# 02_PWR_IN.net
KiCad netlist of a schematic drawn in Altium Designer
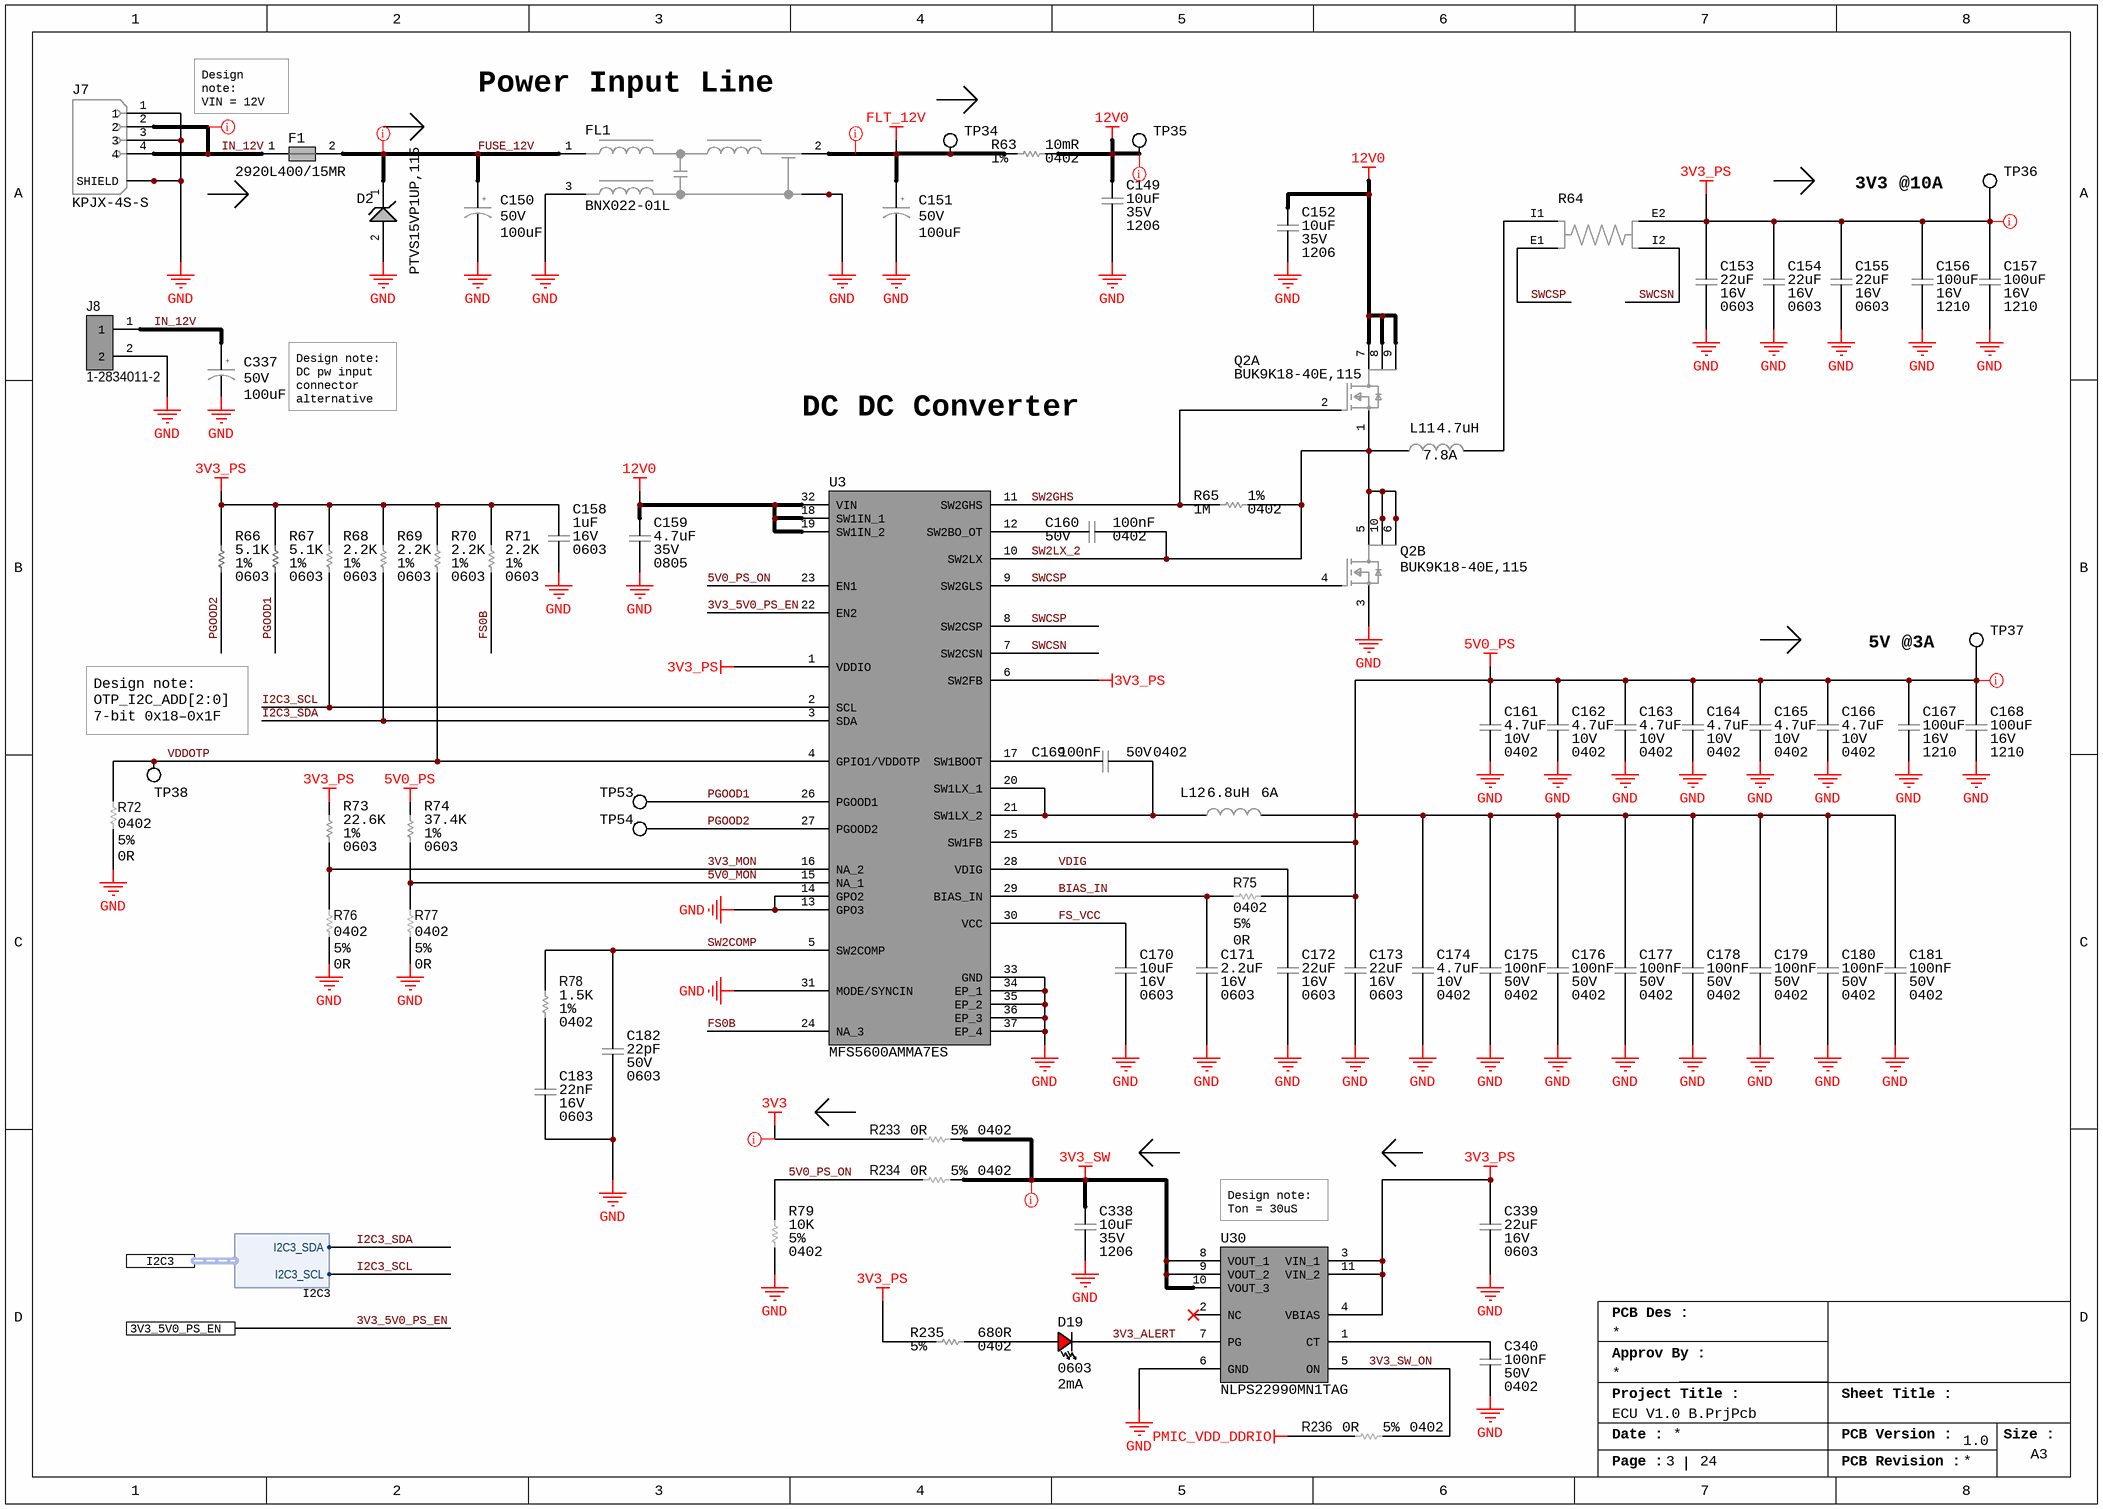
[diagram p0: 02_PWR IN.SchDoc]

(export (version "E")
  (design (tool "Eeschema 10.0.6"))
  (components
    (comp (ref "C149")
      (value "GRM319R6YA106KA12D")
      (footprint "CAP_1206_CAPC3216X16N")
      (description "1206 10 uF 35 V ±10 % Tolerance X5R SMT Multilayer Ceramic Capacitor")
      (fields
        (field (name "MANUFACTURER") "Murata")
        (field (name "TOLERANCE") "10%")
        (field (name "VOLTAGE RATING") "35V")
        (field (name "CAPACITANCE") "10uF")
        (field (name "CASE/PACKAGE") "1206")
      )
      (libsource (lib "Electronic Devices_LIB") (part "CAP_10uF_35V_X5R_1206"))
    )
    (comp (ref "C150")
      (value "UUD1H101MNL1GS")
      (footprint "CAP_POLA_UD(8X10)")
      (description "Radial Can - SMD ALUMINUM ELECTROLYTIC CAPACITOR UUD 50V 100muF ±20% 0.315Dia 8.00mm")
      (fields
        (field (name "MANUFACTURER") "Nichicon")
        (field (name "TOLERANCE") "20%")
        (field (name "VOLTAGE RATING (DC)") "50V")
        (field (name "CAPACITANCE") "100uF")
      )
      (libsource (lib "Electronic Devices_LIB") (part "CAP_100UF_50V_POL"))
    )
    (comp (ref "C151")
      (value "UUD1H101MNL1GS")
      (footprint "CAP_POLA_UD(8X10)")
      (description "Radial Can - SMD ALUMINUM ELECTROLYTIC CAPACITOR UUD 50V 100muF ±20% 0.315Dia 8.00mm")
      (fields
        (field (name "MANUFACTURER") "Nichicon")
        (field (name "TOLERANCE") "20%")
        (field (name "VOLTAGE RATING (DC)") "50V")
        (field (name "CAPACITANCE") "100uF")
      )
      (libsource (lib "Electronic Devices_LIB") (part "CAP_100UF_50V_POL"))
    )
    (comp (ref "C152")
      (value "GRM319R6YA106KA12D")
      (footprint "CAP_1206_CAPC3216X16N")
      (description "1206 10 uF 35 V ±10 % Tolerance X5R SMT Multilayer Ceramic Capacitor")
      (fields
        (field (name "MANUFACTURER") "Murata")
        (field (name "TOLERANCE") "10%")
        (field (name "VOLTAGE RATING") "35V")
        (field (name "CAPACITANCE") "10uF")
        (field (name "CASE/PACKAGE") "1206")
      )
      (libsource (lib "Electronic Devices_LIB") (part "CAP_10uF_35V_X5R_1206"))
    )
    (comp (ref "C153")
      (value "CL10A226MO7JZNC")
      (footprint "CAP_0603_CAPC1608X08N")
      (description "Cap Ceramic 22uF 16V X5R 20% Pad SMD 0603 85C T/R")
      (fields
        (field (name "MANUFACTURER") "Samsung")
        (field (name "TOLERANCE") "20%")
        (field (name "CAPACITANCE") "22uF")
        (field (name "VOLTAGE RATING") "16V")
        (field (name "CASE/PACKAGE") "0603")
      )
      (libsource (lib "Electronic Devices_LIB") (part "CAP_22UF_16V_X5R_0603"))
    )
    (comp (ref "C154")
      (value "CL10A226MO7JZNC")
      (footprint "CAP_0603_CAPC1608X08N")
      (description "Cap Ceramic 22uF 16V X5R 20% Pad SMD 0603 85C T/R")
      (fields
        (field (name "MANUFACTURER") "Samsung")
        (field (name "TOLERANCE") "20%")
        (field (name "CAPACITANCE") "22uF")
        (field (name "VOLTAGE RATING") "16V")
        (field (name "CASE/PACKAGE") "0603")
      )
      (libsource (lib "Electronic Devices_LIB") (part "CAP_22UF_16V_X5R_0603"))
    )
    (comp (ref "C155")
      (value "CL10A226MO7JZNC")
      (footprint "CAP_0603_CAPC1608X08N")
      (description "Cap Ceramic 22uF 16V X5R 20% Pad SMD 0603 85C T/R")
      (fields
        (field (name "MANUFACTURER") "Samsung")
        (field (name "TOLERANCE") "20%")
        (field (name "CAPACITANCE") "22uF")
        (field (name "VOLTAGE RATING") "16V")
        (field (name "CASE/PACKAGE") "0603")
      )
      (libsource (lib "Electronic Devices_LIB") (part "CAP_22UF_16V_X5R_0603"))
    )
    (comp (ref "C156")
      (value "EMK325ABJ107MM-T")
      (footprint "CAP_1210_CAPC3225X270N")
      (description "Multilayer Ceramic Capacitor, 100 uF, 16 V, ± 20%, X5R, 1210 [3225 Metric]")
      (fields
        (field (name "MANUFACTURER") "Taiyo Yuden")
        (field (name "TOLERANCE") "20%")
        (field (name "VOLTAGE RATING") "16V")
        (field (name "CAPACITANCE") "100uF")
        (field (name "CASE/PACKAGE") "1210")
      )
      (libsource (lib "Electronic Devices_LIB") (part "CAP_100UF_16V_X5R_1210"))
    )
    (comp (ref "C157")
      (value "EMK325ABJ107MM-T")
      (footprint "CAP_1210_CAPC3225X270N")
      (description "Multilayer Ceramic Capacitor, 100 uF, 16 V, ± 20%, X5R, 1210 [3225 Metric]")
      (fields
        (field (name "MANUFACTURER") "Taiyo Yuden")
        (field (name "TOLERANCE") "20%")
        (field (name "VOLTAGE RATING") "16V")
        (field (name "CAPACITANCE") "100uF")
        (field (name "CASE/PACKAGE") "1210")
      )
      (libsource (lib "Electronic Devices_LIB") (part "CAP_100UF_16V_X5R_1210"))
    )
    (comp (ref "C158")
      (value "CL10A105KO8NNNC")
      (footprint "CAP_0603_CAPC1608X08N")
      (description "CAP CER 1UF 16V X5R 0603")
      (fields
        (field (name "MANUFACTURER") "Samsung")
        (field (name "TOLERANCE") "10%")
        (field (name "VOLTAGE RATING") "16V")
        (field (name "CAPACITANCE") "1uF")
        (field (name "CASE/PACKAGE") "0603")
      )
      (libsource (lib "Electronic Devices_LIB") (part "CAP_1UF_16V_X5R_0603"))
    )
    (comp (ref "C159")
      (value "CL21A475KLCLQNC")
      (footprint "CAP_0805_CAPC2012X12N")
      (description "CL Series 0805 35 V 4.7 uF ±10% Tolerance X5R Multilayer Ceramic Chip Capacitor")
      (fields
        (field (name "MANUFACTURER") "Samsung")
        (field (name "TOLERANCE") "10%")
        (field (name "VOLTAGE RATING") "35V")
        (field (name "CAPACITANCE") "4.7uF")
        (field (name "CASE/PACKAGE") "0805")
      )
      (libsource (lib "Electronic Devices_LIB") (part "CAP_4.7uF_35V_X5R_0805"))
    )
    (comp (ref "C160")
      (value "GRM155R71H104KE14D")
      (footprint "CAP_0402_CAPC1005X05N")
      (description "Multilayer Ceramic Capacitor, 0.1 uF, 16 V, ± 10%, X7R, 0402 [1005 Metric]")
      (fields
        (field (name "MANUFACTURER") "Murata")
        (field (name "TOLERANCE") "10%")
        (field (name "VOLTAGE RATING") "50V")
        (field (name "CAPACITANCE") "100nF")
        (field (name "CASE/PACKAGE") "0402")
      )
      (libsource (lib "Electronic Devices_LIB") (part "CAP_100NF_50V_X7R_0402"))
    )
    (comp (ref "C161")
      (value "CL05A475KP5NRNC")
      (footprint "CAP_0402_CAPC1005X05N")
      (description "Multilayer Ceramic Capacitor, 4.7 uF, 10 V, ± 10%, X5R, 0402 [1005 Metric]")
      (fields
        (field (name "MANUFACTURER") "Samsung")
        (field (name "TOLERANCE") "10%")
        (field (name "CAPACITANCE") "4.7uF")
        (field (name "VOLTAGE RATING") "10V")
        (field (name "CASE/PACKAGE") "0402")
      )
      (libsource (lib "Electronic Devices_LIB") (part "CAP_4.7UF_10V_X5R_0402"))
    )
    (comp (ref "C162")
      (value "CL05A475KP5NRNC")
      (footprint "CAP_0402_CAPC1005X05N")
      (description "Multilayer Ceramic Capacitor, 4.7 uF, 10 V, ± 10%, X5R, 0402 [1005 Metric]")
      (fields
        (field (name "MANUFACTURER") "Samsung")
        (field (name "TOLERANCE") "10%")
        (field (name "CAPACITANCE") "4.7uF")
        (field (name "VOLTAGE RATING") "10V")
        (field (name "CASE/PACKAGE") "0402")
      )
      (libsource (lib "Electronic Devices_LIB") (part "CAP_4.7UF_10V_X5R_0402"))
    )
    (comp (ref "C163")
      (value "CL05A475KP5NRNC")
      (footprint "CAP_0402_CAPC1005X05N")
      (description "Multilayer Ceramic Capacitor, 4.7 uF, 10 V, ± 10%, X5R, 0402 [1005 Metric]")
      (fields
        (field (name "MANUFACTURER") "Samsung")
        (field (name "TOLERANCE") "10%")
        (field (name "CAPACITANCE") "4.7uF")
        (field (name "VOLTAGE RATING") "10V")
        (field (name "CASE/PACKAGE") "0402")
      )
      (libsource (lib "Electronic Devices_LIB") (part "CAP_4.7UF_10V_X5R_0402"))
    )
    (comp (ref "C164")
      (value "CL05A475KP5NRNC")
      (footprint "CAP_0402_CAPC1005X05N")
      (description "Multilayer Ceramic Capacitor, 4.7 uF, 10 V, ± 10%, X5R, 0402 [1005 Metric]")
      (fields
        (field (name "MANUFACTURER") "Samsung")
        (field (name "TOLERANCE") "10%")
        (field (name "CAPACITANCE") "4.7uF")
        (field (name "VOLTAGE RATING") "10V")
        (field (name "CASE/PACKAGE") "0402")
      )
      (libsource (lib "Electronic Devices_LIB") (part "CAP_4.7UF_10V_X5R_0402"))
    )
    (comp (ref "C165")
      (value "CL05A475KP5NRNC")
      (footprint "CAP_0402_CAPC1005X05N")
      (description "Multilayer Ceramic Capacitor, 4.7 uF, 10 V, ± 10%, X5R, 0402 [1005 Metric]")
      (fields
        (field (name "MANUFACTURER") "Samsung")
        (field (name "TOLERANCE") "10%")
        (field (name "CAPACITANCE") "4.7uF")
        (field (name "VOLTAGE RATING") "10V")
        (field (name "CASE/PACKAGE") "0402")
      )
      (libsource (lib "Electronic Devices_LIB") (part "CAP_4.7UF_10V_X5R_0402"))
    )
    (comp (ref "C166")
      (value "CL05A475KP5NRNC")
      (footprint "CAP_0402_CAPC1005X05N")
      (description "Multilayer Ceramic Capacitor, 4.7 uF, 10 V, ± 10%, X5R, 0402 [1005 Metric]")
      (fields
        (field (name "MANUFACTURER") "Samsung")
        (field (name "TOLERANCE") "10%")
        (field (name "CAPACITANCE") "4.7uF")
        (field (name "VOLTAGE RATING") "10V")
        (field (name "CASE/PACKAGE") "0402")
      )
      (libsource (lib "Electronic Devices_LIB") (part "CAP_4.7UF_10V_X5R_0402"))
    )
    (comp (ref "C167")
      (value "EMK325ABJ107MM-T")
      (footprint "CAP_1210_CAPC3225X270N")
      (description "Multilayer Ceramic Capacitor, 100 uF, 16 V, ± 20%, X5R, 1210 [3225 Metric]")
      (fields
        (field (name "MANUFACTURER") "Taiyo Yuden")
        (field (name "TOLERANCE") "20%")
        (field (name "VOLTAGE RATING") "16V")
        (field (name "CAPACITANCE") "100uF")
        (field (name "CASE/PACKAGE") "1210")
      )
      (libsource (lib "Electronic Devices_LIB") (part "CAP_100UF_16V_X5R_1210"))
    )
    (comp (ref "C168")
      (value "EMK325ABJ107MM-T")
      (footprint "CAP_1210_CAPC3225X270N")
      (description "Multilayer Ceramic Capacitor, 100 uF, 16 V, ± 20%, X5R, 1210 [3225 Metric]")
      (fields
        (field (name "MANUFACTURER") "Taiyo Yuden")
        (field (name "TOLERANCE") "20%")
        (field (name "VOLTAGE RATING") "16V")
        (field (name "CAPACITANCE") "100uF")
        (field (name "CASE/PACKAGE") "1210")
      )
      (libsource (lib "Electronic Devices_LIB") (part "CAP_100UF_16V_X5R_1210"))
    )
    (comp (ref "C169")
      (value "GRM155R71H104KE14D")
      (footprint "CAP_0402_CAPC1005X05N")
      (description "Multilayer Ceramic Capacitor, 0.1 uF, 16 V, ± 10%, X7R, 0402 [1005 Metric]")
      (fields
        (field (name "MANUFACTURER") "Murata")
        (field (name "TOLERANCE") "10%")
        (field (name "VOLTAGE RATING") "50V")
        (field (name "CAPACITANCE") "100nF")
        (field (name "CASE/PACKAGE") "0402")
      )
      (libsource (lib "Electronic Devices_LIB") (part "CAP_100NF_50V_X7R_0402"))
    )
    (comp (ref "C170")
      (value "GRM188R61C106MAALD")
      (footprint "CAP_0603_CAPC1608X08N")
      (description "0603 10 uF 16 V ±20% Tolerance X5R Multilayer Ceramic Chip Capacitor")
      (fields
        (field (name "MANUFACTURER") "Murata")
        (field (name "TOLERANCE") "20%")
        (field (name "VOLTAGE RATING") "16V")
        (field (name "CAPACITANCE") "10uF")
        (field (name "CASE/PACKAGE") "0603")
      )
      (libsource (lib "Electronic Devices_LIB") (part "CAP_10UF_16V_X5R_0603"))
    )
    (comp (ref "C171")
      (value "EMK107BB7225KA-T")
      (footprint "CAP_0603_CAPC1608X08N")
      (description "Multilayer Ceramic Capacitors (High dielectric type), 16V, 2.2 uF, ± 10 %, 0603, X7R, RoHS")
      (fields
        (field (name "MANUFACTURER") "Taiyo Yuden")
        (field (name "TOLERANCE") "10%")
        (field (name "CASE/PACKAGE") "0603")
        (field (name "CAPACITANCE") "2.2uF")
        (field (name "VOLTAGE RATING") "16V")
      )
      (libsource (lib "Electronic Devices_LIB") (part "CAP_2.2UF_16V_X7R_0603"))
    )
    (comp (ref "C172")
      (value "CL10A226MO7JZNC")
      (footprint "CAP_0603_CAPC1608X08N")
      (description "Cap Ceramic 22uF 16V X5R 20% Pad SMD 0603 85C T/R")
      (fields
        (field (name "MANUFACTURER") "Samsung")
        (field (name "TOLERANCE") "20%")
        (field (name "CAPACITANCE") "22uF")
        (field (name "VOLTAGE RATING") "16V")
        (field (name "CASE/PACKAGE") "0603")
      )
      (libsource (lib "Electronic Devices_LIB") (part "CAP_22UF_16V_X5R_0603"))
    )
    (comp (ref "C173")
      (value "CL10A226MO7JZNC")
      (footprint "CAP_0603_CAPC1608X08N")
      (description "Cap Ceramic 22uF 16V X5R 20% Pad SMD 0603 85C T/R")
      (fields
        (field (name "MANUFACTURER") "Samsung")
        (field (name "TOLERANCE") "20%")
        (field (name "CAPACITANCE") "22uF")
        (field (name "VOLTAGE RATING") "16V")
        (field (name "CASE/PACKAGE") "0603")
      )
      (libsource (lib "Electronic Devices_LIB") (part "CAP_22UF_16V_X5R_0603"))
    )
    (comp (ref "C174")
      (value "CL05A475KP5NRNC")
      (footprint "CAP_0402_CAPC1005X05N")
      (description "Multilayer Ceramic Capacitor, 4.7 uF, 10 V, ± 10%, X5R, 0402 [1005 Metric]")
      (fields
        (field (name "MANUFACTURER") "Samsung")
        (field (name "TOLERANCE") "10%")
        (field (name "CAPACITANCE") "4.7uF")
        (field (name "VOLTAGE RATING") "10V")
        (field (name "CASE/PACKAGE") "0402")
      )
      (libsource (lib "Electronic Devices_LIB") (part "CAP_4.7UF_10V_X5R_0402"))
    )
    (comp (ref "C175")
      (value "GRM155R71H104KE14D")
      (footprint "CAP_0402_CAPC1005X05N")
      (description "Multilayer Ceramic Capacitor, 0.1 uF, 16 V, ± 10%, X7R, 0402 [1005 Metric]")
      (fields
        (field (name "MANUFACTURER") "Murata")
        (field (name "TOLERANCE") "10%")
        (field (name "VOLTAGE RATING") "50V")
        (field (name "CAPACITANCE") "100nF")
        (field (name "CASE/PACKAGE") "0402")
      )
      (libsource (lib "Electronic Devices_LIB") (part "CAP_100NF_50V_X7R_0402"))
    )
    (comp (ref "C176")
      (value "GRM155R71H104KE14D")
      (footprint "CAP_0402_CAPC1005X05N")
      (description "Multilayer Ceramic Capacitor, 0.1 uF, 16 V, ± 10%, X7R, 0402 [1005 Metric]")
      (fields
        (field (name "MANUFACTURER") "Murata")
        (field (name "TOLERANCE") "10%")
        (field (name "VOLTAGE RATING") "50V")
        (field (name "CAPACITANCE") "100nF")
        (field (name "CASE/PACKAGE") "0402")
      )
      (libsource (lib "Electronic Devices_LIB") (part "CAP_100NF_50V_X7R_0402"))
    )
    (comp (ref "C177")
      (value "GRM155R71H104KE14D")
      (footprint "CAP_0402_CAPC1005X05N")
      (description "Multilayer Ceramic Capacitor, 0.1 uF, 16 V, ± 10%, X7R, 0402 [1005 Metric]")
      (fields
        (field (name "MANUFACTURER") "Murata")
        (field (name "TOLERANCE") "10%")
        (field (name "VOLTAGE RATING") "50V")
        (field (name "CAPACITANCE") "100nF")
        (field (name "CASE/PACKAGE") "0402")
      )
      (libsource (lib "Electronic Devices_LIB") (part "CAP_100NF_50V_X7R_0402"))
    )
    (comp (ref "C178")
      (value "GRM155R71H104KE14D")
      (footprint "CAP_0402_CAPC1005X05N")
      (description "Multilayer Ceramic Capacitor, 0.1 uF, 16 V, ± 10%, X7R, 0402 [1005 Metric]")
      (fields
        (field (name "MANUFACTURER") "Murata")
        (field (name "TOLERANCE") "10%")
        (field (name "VOLTAGE RATING") "50V")
        (field (name "CAPACITANCE") "100nF")
        (field (name "CASE/PACKAGE") "0402")
      )
      (libsource (lib "Electronic Devices_LIB") (part "CAP_100NF_50V_X7R_0402"))
    )
    (comp (ref "C179")
      (value "GRM155R71H104KE14D")
      (footprint "CAP_0402_CAPC1005X05N")
      (description "Multilayer Ceramic Capacitor, 0.1 uF, 16 V, ± 10%, X7R, 0402 [1005 Metric]")
      (fields
        (field (name "MANUFACTURER") "Murata")
        (field (name "TOLERANCE") "10%")
        (field (name "VOLTAGE RATING") "50V")
        (field (name "CAPACITANCE") "100nF")
        (field (name "CASE/PACKAGE") "0402")
      )
      (libsource (lib "Electronic Devices_LIB") (part "CAP_100NF_50V_X7R_0402"))
    )
    (comp (ref "C180")
      (value "GRM155R71H104KE14D")
      (footprint "CAP_0402_CAPC1005X05N")
      (description "Multilayer Ceramic Capacitor, 0.1 uF, 16 V, ± 10%, X7R, 0402 [1005 Metric]")
      (fields
        (field (name "MANUFACTURER") "Murata")
        (field (name "TOLERANCE") "10%")
        (field (name "VOLTAGE RATING") "50V")
        (field (name "CAPACITANCE") "100nF")
        (field (name "CASE/PACKAGE") "0402")
      )
      (libsource (lib "Electronic Devices_LIB") (part "CAP_100NF_50V_X7R_0402"))
    )
    (comp (ref "C181")
      (value "GRM155R71H104KE14D")
      (footprint "CAP_0402_CAPC1005X05N")
      (description "Multilayer Ceramic Capacitor, 0.1 uF, 16 V, ± 10%, X7R, 0402 [1005 Metric]")
      (fields
        (field (name "MANUFACTURER") "Murata")
        (field (name "TOLERANCE") "10%")
        (field (name "VOLTAGE RATING") "50V")
        (field (name "CAPACITANCE") "100nF")
        (field (name "CASE/PACKAGE") "0402")
      )
      (libsource (lib "Electronic Devices_LIB") (part "CAP_100NF_50V_X7R_0402"))
    )
    (comp (ref "C182")
      (value "C0603C220J5GACTU")
      (footprint "CAP_0603_CAPC1608X08N")
      (description "Multilayer Ceramic Capacitor, 22 pF, 50 V, ï¿½ 5%, C0G (NP0), 0603 [1608 Metric]")
      (fields
        (field (name "MANUFACTURER") "KEMET")
        (field (name "TOLERANCE") "5%")
        (field (name "VOLTAGE RATING (DC)") "50V")
        (field (name "CAPACITANCE") "22pF")
        (field (name "CASE/PACKAGE") "0603")
      )
      (libsource (lib "Electronic Devices_LIB") (part "CAP_22pF_50V_NP0_0603"))
    )
    (comp (ref "C183")
      (value "C0603C223K4RACTU")
      (footprint "CAP_0603_CAPC1608X08N")
      (description "Multilayer Ceramic Capacitor, 0.022 uF, 16 V, ± 10%, X7R, 0603 [1608 Metric]")
      (fields
        (field (name "MANUFACTURER") "KEMET")
        (field (name "TOLERANCE") "10%")
        (field (name "VOLTAGE RATING (DC)") "16V")
        (field (name "CAPACITANCE") "22nF")
        (field (name "CASE/PACKAGE") "0603")
      )
      (libsource (lib "Electronic Devices_LIB") (part "CAP_22nF_16V_X7R_0603"))
    )
    (comp (ref "C337")
      (value "UUD1H101MNL1GS")
      (footprint "CAP_POLA_UD(8X10)")
      (description "Radial Can - SMD ALUMINUM ELECTROLYTIC CAPACITOR UUD 50V 100muF ±20% 0.315Dia 8.00mm")
      (fields
        (field (name "MANUFACTURER") "Nichicon")
        (field (name "TOLERANCE") "20%")
        (field (name "VOLTAGE RATING (DC)") "50V")
        (field (name "CAPACITANCE") "100uF")
      )
      (libsource (lib "Electronic Devices_LIB") (part "CAP_100UF_50V_POL"))
    )
    (comp (ref "C338")
      (value "GRM319R6YA106KA12D")
      (footprint "CAP_1206_CAPC3216X16N")
      (description "1206 10 uF 35 V ±10 % Tolerance X5R SMT Multilayer Ceramic Capacitor")
      (fields
        (field (name "MANUFACTURER") "Murata")
        (field (name "TOLERANCE") "10%")
        (field (name "VOLTAGE RATING") "35V")
        (field (name "CAPACITANCE") "10uF")
        (field (name "CASE/PACKAGE") "1206")
      )
      (libsource (lib "Electronic Devices_LIB") (part "CAP_10uF_35V_X5R_1206"))
    )
    (comp (ref "C339")
      (value "CL10A226MO7JZNC")
      (footprint "CAP_0603_CAPC1608X08N")
      (description "Cap Ceramic 22uF 16V X5R 20% Pad SMD 0603 85C T/R")
      (fields
        (field (name "MANUFACTURER") "Samsung")
        (field (name "TOLERANCE") "20%")
        (field (name "CAPACITANCE") "22uF")
        (field (name "VOLTAGE RATING") "16V")
        (field (name "CASE/PACKAGE") "0603")
      )
      (libsource (lib "Electronic Devices_LIB") (part "CAP_22UF_16V_X5R_0603"))
    )
    (comp (ref "C340")
      (value "GRM155R71H104KE14D")
      (footprint "CAP_0402_CAPC1005X05N")
      (description "Multilayer Ceramic Capacitor, 0.1 uF, 16 V, ± 10%, X7R, 0402 [1005 Metric]")
      (fields
        (field (name "MANUFACTURER") "Murata")
        (field (name "TOLERANCE") "10%")
        (field (name "VOLTAGE RATING") "50V")
        (field (name "CAPACITANCE") "100nF")
        (field (name "CASE/PACKAGE") "0402")
      )
      (libsource (lib "Electronic Devices_LIB") (part "CAP_100NF_50V_X7R_0402"))
    )
    (comp (ref "D2")
      (value "PTVS15VP1UP,115")
      (footprint "PMEG3050EP115")
      (description "TVS DIODE 15VWM 24.4VC SOD128")
      (fields (field (name "MANUFACTURER") "Nexperia"))
      (libsource (lib "Electronic Devices_LIB") (part "DIO_TVS_24.4V_PTVS15VP1UP,115"))
    )
    (comp (ref "D19")
      (value "LTST-C193KRKT-2A")
      (footprint "LED_0603-RED-0.75mm")
      (description "Led Red Clear 0603 Smd")
      (fields
        (field (name "MANUFACTURER") "Vishay Lite-On")
        (field (name "CASE/PACKAGE") "0603")
        (field (name "TEST CURRENT") "2mA")
      )
      (libsource (lib "Electronic Devices_LIB") (part "LED_DIO_RED_2mA_0603_LTST-C193KRKT-2A"))
    )
    (comp (ref "F1")
      (value "2920L400/15MR")
      (footprint "2920L07560MR")
      (description "PTC Resettable Fuse 4A(hold) 8A(trip) 15VDC 40A 1.5W 4s 0.01Ohm SMD Solder Pad 2920 T/R")
      (fields (field (name "MANUFACTURER") "Littelfuse"))
      (libsource (lib "Electronic Devices_LIB") (part "FUSE_PTC_8A_2920L400/15MR"))
    )
    (comp (ref "FL1")
      (value "BNX022-01L")
      (footprint "FILTER_BNX022-01L")
      (description "EMI Filter 1MHz to 1000MHz 35dB 10A 50VDC Flat Style SMD Embossed T/R")
      (fields (field (name "MANUFACTURER") "Murata"))
      (libsource (lib "Electronic Devices_LIB") (part "FILTER_EMI_50VDC_10A_BNX022-01L"))
    )
    (comp (ref "J7")
      (value "KPJX-4S-S")
      (footprint "CONN_DC_KYCON_KPJX-4S-S")
      (description "Conn Power SKT 4 POS Solder ST Thru-Hole 4 Terminal 1 Port")
      (fields (field (name "MANUFACTURER") "Kycon"))
      (libsource (lib "Electronic Devices_LIB") (part "CONN_DC_JACK_PWR_KPJX-4S-S"))
    )
    (comp (ref "J8")
      (value "1-2834011-2")
      (footprint "CONN_TBLOCK_128340112")
      (description "2POS3.5MMTOPENTRYSCREWLESSC")
      (fields (field (name "MANUFACTURER") "TE Connectivity") (field (name "VOLTAGE") "300V"))
      (libsource (lib "Electronic Devices_LIB") (part "CONN_TBLOCK_2P_3.5mm_1-2834011-2"))
    )
    (comp (ref "L11")
      (value "SPM7054VT-4R7M-D")
      (footprint "SPM7054VT")
      (description "Inductor Power Shielded Wirewound 4.7uH 20% 100KHz Metal 7.8A 0.01826Ohm DCR Automotive T/R")
      (fields
        (field (name "MANUFACTURER") "TDK")
        (field (name "CURRENT RATING") "7.8A")
        (field (name "INDUCTANCE") "4.7uH")
      )
      (libsource (lib "Electronic Devices_LIB") (part "IND_4.7uH_7.8A_SPM7054VT-4R7M-D"))
    )
    (comp (ref "L12")
      (value "74437368068")
      (footprint "WE-LHMI_104048")
      (description "WE-LHMI; 6800 nH; Composite Iron Multilayer SMD Inductor; 1040 Case; .013GHz 6A")
      (fields
        (field (name "MANUFACTURER") "Wurth Electronics")
        (field (name "TOLERANCE") "20%")
        (field (name "MAX DC CURRENT") "6A")
        (field (name "INDUCTANCE") "6.8uH")
      )
      (libsource (lib "Electronic Devices_LIB") (part "IND_6.8uH_6A_74437368068"))
    )
    (comp (ref "Q2")
      (value "BUK9K18-40E,115")
      (footprint "BUK9K1840E115")
      (description "Transistor MOSFET Array Dual N -CH 40V 30A 8-Pin LFPAK-56D T/R")
      (fields (field (name "MANUFACTURER") "Nexperia"))
      (libsource (lib "Electronic Devices_LIB") (part "TRANS_FET_CH__N_40V_30A_BUK9K18-40E,115"))
    )
    (comp (ref "R63")
      (value "ERJ-2LWFR010X")
      (footprint "RES_0603_RESC1608X04N")
      (description "Res Current Sense Thick Film 0402 0.01 Ohm 1% 1/5W 0ppm/°C to 500ppm/°C Molded T/R")
      (fields
        (field (name "MANUFACTURER") "Panasonic")
        (field (name "TOLERANCE") "1%")
        (field (name "RESISTANCE") "10mR")
        (field (name "CASE/PACKAGE") "0402")
      )
      (libsource (lib "Electronic Devices_LIB") (part "RES_10mR_1%_0.05W_0402"))
    )
    (comp (ref "R64")
      (value "WSK2512R0100FEA")
      (footprint "RES_WSK2512R0100FEA")
      (description "Fixed Resistor, Metal Strip, 1W, 0.01ohm, 0.1V, 1% +/-Tol, 35ppm/Cel, Surface Mount, 2512")
      (fields (field (name "MANUFACTURER") "Vishay") (field (name "TOLERANCE") "1%"))
      (libsource (lib "Electronic Devices_LIB") (part "RES_10mR_1%_1W_2512"))
    )
    (comp (ref "R65")
      (value "CR0402-FX-1004GLF")
      (footprint "RES_0402_RESC1005X04N")
      (description "Res Thick Film 0402 1M Ohm 1% 1/16W ±100ppm/°C Molded SMD SMD Paper Tape on Plastic Reel")
      (fields
        (field (name "MANUFACTURER") "Bourns")
        (field (name "RESISTANCE") "1M")
        (field (name "TOLERANCE") "1%")
        (field (name "CASE/PACKAGE") "0402")
      )
      (libsource (lib "Electronic Devices_LIB") (part "RES_1M_1%_63mW_0402"))
    )
    (comp (ref "R66")
      (value "RC0603FR-075K1L")
      (footprint "RES_0603_RESC1608X04N")
      (description "SMD Chip Resistor, 5.1 kOhm, ± 1%, 100 mW, 0603 [1608 Metric], Thick Film, General Purpose")
      (fields
        (field (name "MANUFACTURER") "Yageo")
        (field (name "TOLERANCE") "1%")
        (field (name "RESISTANCE") "5.1K")
        (field (name "CASE/PACKAGE") "0603")
      )
      (libsource (lib "Electronic Devices_LIB") (part "RES_5.1K_1%_100mW_0603"))
    )
    (comp (ref "R67")
      (value "RC0603FR-075K1L")
      (footprint "RES_0603_RESC1608X04N")
      (description "SMD Chip Resistor, 5.1 kOhm, ± 1%, 100 mW, 0603 [1608 Metric], Thick Film, General Purpose")
      (fields
        (field (name "MANUFACTURER") "Yageo")
        (field (name "TOLERANCE") "1%")
        (field (name "RESISTANCE") "5.1K")
        (field (name "CASE/PACKAGE") "0603")
      )
      (libsource (lib "Electronic Devices_LIB") (part "RES_5.1K_1%_100mW_0603"))
    )
    (comp (ref "R68")
      (value "RC0603FR-072K2L")
      (footprint "RES_0603_RESC1608X04N")
      (description "SMD Chip Resistor, 2.2 Kohm, ½ 1%, 100 Mw, 0603 [1608 Metric], Thick Film, General Purpose")
      (fields
        (field (name "MANUFACTURER") "Yageo")
        (field (name "TOLERANCE") "1%")
        (field (name "RESISTANCE") "2.2K")
        (field (name "CASE/PACKAGE") "0603")
      )
      (libsource (lib "Electronic Devices_LIB") (part "RES_2.2K_1%_100mW_0603"))
    )
    (comp (ref "R69")
      (value "RC0603FR-072K2L")
      (footprint "RES_0603_RESC1608X04N")
      (description "SMD Chip Resistor, 2.2 Kohm, ½ 1%, 100 Mw, 0603 [1608 Metric], Thick Film, General Purpose")
      (fields
        (field (name "MANUFACTURER") "Yageo")
        (field (name "TOLERANCE") "1%")
        (field (name "RESISTANCE") "2.2K")
        (field (name "CASE/PACKAGE") "0603")
      )
      (libsource (lib "Electronic Devices_LIB") (part "RES_2.2K_1%_100mW_0603"))
    )
    (comp (ref "R70")
      (value "RC0603FR-072K2L")
      (footprint "RES_0603_RESC1608X04N")
      (description "SMD Chip Resistor, 2.2 Kohm, ½ 1%, 100 Mw, 0603 [1608 Metric], Thick Film, General Purpose")
      (fields
        (field (name "MANUFACTURER") "Yageo")
        (field (name "TOLERANCE") "1%")
        (field (name "RESISTANCE") "2.2K")
        (field (name "CASE/PACKAGE") "0603")
      )
      (libsource (lib "Electronic Devices_LIB") (part "RES_2.2K_1%_100mW_0603"))
    )
    (comp (ref "R71")
      (value "RC0603FR-072K2L")
      (footprint "RES_0603_RESC1608X04N")
      (description "SMD Chip Resistor, 2.2 Kohm, ½ 1%, 100 Mw, 0603 [1608 Metric], Thick Film, General Purpose")
      (fields
        (field (name "MANUFACTURER") "Yageo")
        (field (name "TOLERANCE") "1%")
        (field (name "RESISTANCE") "2.2K")
        (field (name "CASE/PACKAGE") "0603")
      )
      (libsource (lib "Electronic Devices_LIB") (part "RES_2.2K_1%_100mW_0603"))
    )
    (comp (ref "R72")
      (value "ERJ-2GE0R00X")
      (footprint "RES_0402_RESC1005X04N")
      (description "SMD Chip Resistor, Jumper, 0 ohm, 100 mW, 0402 [1005 Metric], Thick Film, General Purpose")
      (fields
        (field (name "MANUFACTURER") "Panasonic")
        (field (name "CASE CODE (IMPERIAL)") "0402")
        (field (name "TOLERANCE") "5%")
        (field (name "RESISTANCE") "0R")
      )
      (libsource (lib "Electronic Devices_LIB") (part "RES_0R_5%_100mW_0402"))
    )
    (comp (ref "R73")
      (value "AC0603FR-0722K6L")
      (footprint "RES_0603_RESC1608X04N")
      (description "Res Thick Film 0603 22.6K Ohm 1% 0.1W(1/10W) ±100ppm/C Pad SMD Automotive T/R")
      (fields
        (field (name "MANUFACTURER") "Yageo")
        (field (name "TOLERANCE") "1%")
        (field (name "RESISTANCE") "22.6K")
        (field (name "CASE/PACKAGE") "0603")
      )
      (libsource (lib "Electronic Devices_LIB") (part "RES_22.6K_1%_100mW_0603"))
    )
    (comp (ref "R74")
      (value "RC0603FR-0737K4L")
      (footprint "RES_0603_RESC1608X04N")
      (description "SMD Chip Resistor, 37.4 kOhm, ± 1%, 100 mW, 0603 [1608 Metric], Thick Film, General Purpose")
      (fields
        (field (name "MANUFACTURER") "Yageo")
        (field (name "TOLERANCE") "1%")
        (field (name "RESISTANCE") "37.4K")
        (field (name "CASE/PACKAGE") "0603")
      )
      (libsource (lib "Electronic Devices_LIB") (part "RES_37.4K_1%_100mW_0603"))
    )
    (comp (ref "R75")
      (value "ERJ-2GE0R00X")
      (footprint "RES_0402_RESC1005X04N")
      (description "SMD Chip Resistor, Jumper, 0 ohm, 100 mW, 0402 [1005 Metric], Thick Film, General Purpose")
      (fields
        (field (name "MANUFACTURER") "Panasonic")
        (field (name "CASE CODE (IMPERIAL)") "0402")
        (field (name "TOLERANCE") "5%")
        (field (name "RESISTANCE") "0R")
      )
      (libsource (lib "Electronic Devices_LIB") (part "RES_0R_5%_100mW_0402"))
    )
    (comp (ref "R76")
      (value "ERJ-2GE0R00X")
      (footprint "RES_0402_RESC1005X04N")
      (description "SMD Chip Resistor, Jumper, 0 ohm, 100 mW, 0402 [1005 Metric], Thick Film, General Purpose")
      (fields
        (field (name "MANUFACTURER") "Panasonic")
        (field (name "CASE CODE (IMPERIAL)") "0402")
        (field (name "TOLERANCE") "5%")
        (field (name "RESISTANCE") "0R")
      )
      (libsource (lib "Electronic Devices_LIB") (part "RES_0R_5%_100mW_0402"))
    )
    (comp (ref "R77")
      (value "ERJ-2GE0R00X")
      (footprint "RES_0402_RESC1005X04N")
      (description "SMD Chip Resistor, Jumper, 0 ohm, 100 mW, 0402 [1005 Metric], Thick Film, General Purpose")
      (fields
        (field (name "MANUFACTURER") "Panasonic")
        (field (name "CASE CODE (IMPERIAL)") "0402")
        (field (name "TOLERANCE") "5%")
        (field (name "RESISTANCE") "0R")
      )
      (libsource (lib "Electronic Devices_LIB") (part "RES_0R_5%_100mW_0402"))
    )
    (comp (ref "R78")
      (value "CR0402-FX-1501GLF")
      (footprint "RES_0402_RESC1005X04N")
      (description "Res Thick Film 0402 1.5K Ohm 1% 1/16W ±100ppm/°C Molded SMD SMD Paper Tape on Plastic Reel")
      (fields
        (field (name "MANUFACTURER") "Bourns")
        (field (name "RESISTANCE") "1.5K")
        (field (name "TOLERANCE") "1%")
        (field (name "CASE/PACKAGE") "0402")
      )
      (libsource (lib "Electronic Devices_LIB") (part "RES_1.5K_1%_63mW_0402"))
    )
    (comp (ref "R79")
      (value "ERJ-2GEJ103X")
      (footprint "RES_0402_RESC1005X04N")
      (description "Res Thick Film 0402 10K Ohm 5% 1/10W ±200ppm/°C Molded SMD Punched Carrier T/R")
      (fields
        (field (name "MANUFACTURER") "Panasonic")
        (field (name "TOLERANCE") "5%")
        (field (name "RESISTANCE") "10K")
        (field (name "CASE/PACKAGE") "0402")
      )
      (libsource (lib "Electronic Devices_LIB") (part "RES_10K_5%_100mW_0402"))
    )
    (comp (ref "R233")
      (value "ERJ-2GE0R00X")
      (footprint "RES_0402_RESC1005X04N")
      (description "SMD Chip Resistor, Jumper, 0 ohm, 100 mW, 0402 [1005 Metric], Thick Film, General Purpose")
      (fields
        (field (name "MANUFACTURER") "Panasonic")
        (field (name "CASE CODE (IMPERIAL)") "0402")
        (field (name "TOLERANCE") "5%")
        (field (name "RESISTANCE") "0R")
      )
      (libsource (lib "Electronic Devices_LIB") (part "RES_0R_5%_100mW_0402"))
    )
    (comp (ref "R234")
      (value "ERJ-2GE0R00X")
      (footprint "RES_0402_RESC1005X04N")
      (description "SMD Chip Resistor, Jumper, 0 ohm, 100 mW, 0402 [1005 Metric], Thick Film, General Purpose")
      (fields
        (field (name "MANUFACTURER") "Panasonic")
        (field (name "CASE CODE (IMPERIAL)") "0402")
        (field (name "TOLERANCE") "5%")
        (field (name "RESISTANCE") "0R")
      )
      (libsource (lib "Electronic Devices_LIB") (part "RES_0R_5%_100mW_0402"))
    )
    (comp (ref "R235")
      (value "ERJ-2GEJ681X")
      (footprint "RES_0402_RESC1005X04N")
      (description "SMD Chip Resistor, 680 Ohm, ± 5%, 100 mW, 0402 [1005 Metric], Thick Film, General Purpose")
      (fields
        (field (name "MANUFACTURER") "Panasonic")
        (field (name "TOLERANCE") "5%")
        (field (name "RESISTANCE") "680R")
        (field (name "CASE/PACKAGE") "0402")
      )
      (libsource (lib "Electronic Devices_LIB") (part "RES_680R_5%_100mW_0402"))
    )
    (comp (ref "R236")
      (value "ERJ-2GE0R00X")
      (footprint "RES_0402_RESC1005X04N")
      (description "SMD Chip Resistor, Jumper, 0 ohm, 100 mW, 0402 [1005 Metric], Thick Film, General Purpose")
      (fields
        (field (name "MANUFACTURER") "Panasonic")
        (field (name "CASE CODE (IMPERIAL)") "0402")
        (field (name "TOLERANCE") "5%")
        (field (name "RESISTANCE") "0R")
      )
      (libsource (lib "Electronic Devices_LIB") (part "RES_0R_5%_100mW_0402"))
    )
    (comp (ref "TP34")
      (value "NO COMPONENT")
      (footprint "TP_PAD_0.5MM_SMD_ROUND")
      (description "Test Point, SMD pad, round, 1.5mm, 1.6mm, 3mm diameter")
      (libsource (lib "Electronic Devices_LIB") (part "TP_PAD_SMD_SMALL"))
    )
    (comp (ref "TP35")
      (value "NO COMPONENT")
      (footprint "TP_PAD_0.5MM_SMD_ROUND")
      (description "Test Point, SMD pad, round, 1.5mm, 1.6mm, 3mm diameter")
      (libsource (lib "Electronic Devices_LIB") (part "TP_PAD_SMD_SMALL"))
    )
    (comp (ref "TP36")
      (value "NO COMPONENT")
      (footprint "TP_PAD_0.5MM_SMD_ROUND")
      (description "Test Point, SMD pad, round, 1.5mm, 1.6mm, 3mm diameter")
      (libsource (lib "Electronic Devices_LIB") (part "TP_PAD_SMD_SMALL"))
    )
    (comp (ref "TP37")
      (value "NO COMPONENT")
      (footprint "TP_PAD_0.5MM_SMD_ROUND")
      (description "Test Point, SMD pad, round, 1.5mm, 1.6mm, 3mm diameter")
      (libsource (lib "Electronic Devices_LIB") (part "TP_PAD_SMD_SMALL"))
    )
    (comp (ref "TP38")
      (value "NO COMPONENT")
      (footprint "TP_PAD_0.5MM_SMD_ROUND")
      (description "Test Point, SMD pad, round, 1.5mm, 1.6mm, 3mm diameter")
      (libsource (lib "Electronic Devices_LIB") (part "TP_PAD_SMD_SMALL"))
    )
    (comp (ref "TP53")
      (value "NO COMPONENT")
      (footprint "TP_PAD_0.5MM_SMD_ROUND")
      (description "Test Point, SMD pad, round, 1.5mm, 1.6mm, 3mm diameter")
      (libsource (lib "Electronic Devices_LIB") (part "TP_PAD_SMD_SMALL"))
    )
    (comp (ref "TP54")
      (value "NO COMPONENT")
      (footprint "TP_PAD_0.5MM_SMD_ROUND")
      (description "Test Point, SMD pad, round, 1.5mm, 1.6mm, 3mm diameter")
      (libsource (lib "Electronic Devices_LIB") (part "TP_PAD_SMD_SMALL"))
    )
    (comp (ref "U3")
      (value "MFS5600AMMA7ES")
      (footprint "MFS5600AMMA7ES")
      (description "Power Management, 36 V, 2 Step-Down DC-DC Converters, 2 Regulated Outputs, 32 Pins, HVQFN-EP")
      (fields (field (name "MANUFACTURER") "NXP Semiconductors"))
      (libsource (lib "Electronic Devices_LIB") (part "IC_REG_BUCK_MFS5600AMMA7ES"))
    )
    (comp (ref "U30")
      (value "NLPS22990MN1TAG")
      (footprint "SON50P200X300X80-11N")
      (description "5.5 V, 10 A, 3.9 mΩ On-Resistance Load Switch 5.5 V, 10 A, 3.9 mOhm On-Resistance")
      (fields (field (name "MANUFACTURER") "onsemi"))
      (libsource (lib "Electronic Devices_LIB") (part "IC_LOAD_SW_NLPS22990MN1TAG"))
    )
  )
  (nets
    (net (code "2") (name "/3V3_5V0_PS_EN") (class "Default")
      (node (ref "U3") (pin "22") (pinfunction "EN2_22") (pintype "passive"))
    )
    (net (code "3") (name "/3V3_ALERT") (class "Default")
      (node (ref "D19") (pin "1") (pinfunction "C_1") (pintype "passive"))
      (node (ref "U30") (pin "7") (pinfunction "PG_7") (pintype "passive"))
    )
    (net (code "4") (name "/3V3_MON") (class "Default")
      (node (ref "R73") (pin "1") (pinfunction "1_1") (pintype "passive"))
      (node (ref "R76") (pin "2") (pinfunction "2_2") (pintype "passive"))
      (node (ref "U3") (pin "16") (pinfunction "NA_2_16") (pintype "passive"))
    )
    (net (code "5") (name "/3V3_SW_ON") (class "Default")
      (node (ref "R236") (pin "1") (pinfunction "1_1") (pintype "passive"))
      (node (ref "U30") (pin "5") (pinfunction "ON_5") (pintype "passive"))
    )
    (net (code "6") (name "/5V0_MON") (class "Default")
      (node (ref "R74") (pin "1") (pinfunction "1_1") (pintype "passive"))
      (node (ref "R77") (pin "2") (pinfunction "2_2") (pintype "passive"))
      (node (ref "U3") (pin "15") (pinfunction "NA_1_15") (pintype "passive"))
    )
    (net (code "7") (name "/5V0_PS_ON") (class "Default")
      (node (ref "R234") (pin "2") (pinfunction "2_2") (pintype "passive"))
      (node (ref "R79") (pin "1") (pinfunction "1_1") (pintype "passive"))
      (node (ref "U3") (pin "23") (pinfunction "EN1_23") (pintype "passive"))
    )
    (net (code "8") (name "/BIAS_IN") (class "Default")
      (node (ref "C171") (pin "2") (pinfunction "2_2") (pintype "passive"))
      (node (ref "R75") (pin "2") (pinfunction "2_2") (pintype "passive"))
      (node (ref "U3") (pin "29") (pinfunction "BIAS_IN_29") (pintype "passive"))
    )
    (net (code "9") (name "/FS0B") (class "Default")
      (node (ref "R71") (pin "1") (pinfunction "1_1") (pintype "passive"))
      (node (ref "U3") (pin "24") (pinfunction "NA_3_24") (pintype "passive"))
    )
    (net (code "10") (name "/FS_VCC") (class "Default")
      (node (ref "C170") (pin "2") (pinfunction "2_2") (pintype "passive"))
      (node (ref "U3") (pin "30") (pinfunction "VCC_30") (pintype "passive"))
    )
    (net (code "11") (name "/FUSE_12V") (class "Default")
      (node (ref "C150") (pin "1") (pinfunction "1_1") (pintype "passive"))
      (node (ref "D2") (pin "1") (pinfunction "K_1") (pintype "passive"))
      (node (ref "F1") (pin "2") (pinfunction "2_2") (pintype "passive"))
      (node (ref "FL1") (pin "1") (pinfunction "B_1") (pintype "passive"))
    )
    (net (code "12") (name "/I2C3_SCL") (class "Default")
      (node (ref "R68") (pin "1") (pinfunction "1_1") (pintype "passive"))
      (node (ref "U3") (pin "2") (pinfunction "SCL_2") (pintype "passive"))
    )
    (net (code "13") (name "/I2C3_SDA") (class "Default")
      (node (ref "R69") (pin "1") (pinfunction "1_1") (pintype "passive"))
      (node (ref "U3") (pin "3") (pinfunction "SDA_3") (pintype "passive"))
    )
    (net (code "14") (name "/IN_12V") (class "Default")
      (node (ref "C337") (pin "1") (pinfunction "1_1") (pintype "passive"))
      (node (ref "F1") (pin "1") (pinfunction "1_1") (pintype "passive"))
      (node (ref "J7") (pin "2") (pinfunction "2_2") (pintype "passive"))
      (node (ref "J7") (pin "4") (pinfunction "4_4") (pintype "passive"))
      (node (ref "J8") (pin "1") (pinfunction "1_1") (pintype "passive"))
    )
    (net (code "15") (name "/PGOOD1") (class "Default")
      (node (ref "R67") (pin "1") (pinfunction "1_1") (pintype "passive"))
      (node (ref "TP53") (pin "1") (pinfunction "1_1") (pintype "passive"))
      (node (ref "U3") (pin "26") (pinfunction "PGOOD1_26") (pintype "passive"))
    )
    (net (code "16") (name "/PGOOD2") (class "Default")
      (node (ref "R66") (pin "1") (pinfunction "1_1") (pintype "passive"))
      (node (ref "TP54") (pin "1") (pinfunction "1_1") (pintype "passive"))
      (node (ref "U3") (pin "27") (pinfunction "PGOOD2_27") (pintype "passive"))
    )
    (net (code "17") (name "/SW2COMP") (class "Default")
      (node (ref "C182") (pin "2") (pinfunction "2_2") (pintype "passive"))
      (node (ref "R78") (pin "2") (pinfunction "2_2") (pintype "passive"))
      (node (ref "U3") (pin "5") (pinfunction "SW2COMP_5") (pintype "passive"))
    )
    (net (code "18") (name "/SW2GHS") (class "Default")
      (node (ref "Q2") (pin "2") (pinfunction "G1_2") (pintype "passive"))
      (node (ref "R65") (pin "1") (pinfunction "1_1") (pintype "passive"))
      (node (ref "U3") (pin "11") (pinfunction "SW2GHS_11") (pintype "passive"))
    )
    (net (code "19") (name "/SW2LX_2") (class "Default")
      (node (ref "C160") (pin "1") (pinfunction "1_1") (pintype "passive"))
      (node (ref "L11") (pin "1") (pinfunction "1_1") (pintype "passive"))
      (node (ref "Q2") (pin "1") (pinfunction "S1_1") (pintype "passive"))
      (node (ref "Q2") (pin "10") (pinfunction "D2_3_10") (pintype "passive"))
      (node (ref "Q2") (pin "5") (pinfunction "D2_1_5") (pintype "passive"))
      (node (ref "Q2") (pin "6") (pinfunction "D2_2_6") (pintype "passive"))
      (node (ref "R65") (pin "2") (pinfunction "2_2") (pintype "passive"))
      (node (ref "U3") (pin "10") (pinfunction "SW2LX_10") (pintype "passive"))
    )
    (net (code "20") (name "/SWCSN") (class "Default")
      (node (ref "R64") (pin "I2") (pinfunction "I2_I2") (pintype "passive"))
      (node (ref "U3") (pin "7") (pinfunction "SW2CSN_7") (pintype "passive"))
    )
    (net (code "21") (name "/SWCSP") (class "Default")
      (node (ref "Q2") (pin "4") (pinfunction "G2_4") (pintype "passive"))
      (node (ref "R64") (pin "E1") (pinfunction "E1_E1") (pintype "passive"))
      (node (ref "U3") (pin "8") (pinfunction "SW2CSP_8") (pintype "passive"))
      (node (ref "U3") (pin "9") (pinfunction "SW2GLS_9") (pintype "passive"))
    )
    (net (code "22") (name "/VDDOTP") (class "Default")
      (node (ref "R70") (pin "1") (pinfunction "1_1") (pintype "passive"))
      (node (ref "R72") (pin "2") (pinfunction "2_2") (pintype "passive"))
      (node (ref "TP38") (pin "1") (pinfunction "1_1") (pintype "passive"))
      (node (ref "U3") (pin "4") (pinfunction "GPIO1/VDDOTP_4") (pintype "passive"))
    )
    (net (code "23") (name "/VDIG") (class "Default")
      (node (ref "C172") (pin "2") (pinfunction "2_2") (pintype "passive"))
      (node (ref "U3") (pin "28") (pinfunction "VDIG_28") (pintype "passive"))
    )
    (net (code "25") (name "3V3") (class "Default")
      (node (ref "R233") (pin "2") (pinfunction "2_2") (pintype "passive"))
    )
    (net (code "26") (name "3V3_PS") (class "Default")
      (node (ref "C153") (pin "2") (pinfunction "2_2") (pintype "passive"))
      (node (ref "C154") (pin "2") (pinfunction "2_2") (pintype "passive"))
      (node (ref "C155") (pin "2") (pinfunction "2_2") (pintype "passive"))
      (node (ref "C156") (pin "2") (pinfunction "2_2") (pintype "passive"))
      (node (ref "C157") (pin "2") (pinfunction "2_2") (pintype "passive"))
      (node (ref "C158") (pin "2") (pinfunction "2_2") (pintype "passive"))
      (node (ref "C339") (pin "2") (pinfunction "2_2") (pintype "passive"))
      (node (ref "R235") (pin "1") (pinfunction "1_1") (pintype "passive"))
      (node (ref "R64") (pin "E2") (pinfunction "E2_E2") (pintype "passive"))
      (node (ref "R66") (pin "2") (pinfunction "2_2") (pintype "passive"))
      (node (ref "R67") (pin "2") (pinfunction "2_2") (pintype "passive"))
      (node (ref "R68") (pin "2") (pinfunction "2_2") (pintype "passive"))
      (node (ref "R69") (pin "2") (pinfunction "2_2") (pintype "passive"))
      (node (ref "R70") (pin "2") (pinfunction "2_2") (pintype "passive"))
      (node (ref "R71") (pin "2") (pinfunction "2_2") (pintype "passive"))
      (node (ref "R73") (pin "2") (pinfunction "2_2") (pintype "passive"))
      (node (ref "TP36") (pin "1") (pinfunction "1_1") (pintype "passive"))
      (node (ref "U3") (pin "1") (pinfunction "VDDIO_1") (pintype "passive"))
      (node (ref "U3") (pin "6") (pinfunction "SW2FB_6") (pintype "passive"))
      (node (ref "U30") (pin "11") (pinfunction "VIN_2_11") (pintype "passive"))
      (node (ref "U30") (pin "3") (pinfunction "VIN_1_3") (pintype "passive"))
      (node (ref "U30") (pin "4") (pinfunction "VBIAS_4") (pintype "passive"))
    )
    (net (code "27") (name "3V3_SW") (class "Default")
      (node (ref "C338") (pin "2") (pinfunction "2_2") (pintype "passive"))
      (node (ref "R233") (pin "1") (pinfunction "1_1") (pintype "passive"))
      (node (ref "R234") (pin "1") (pinfunction "1_1") (pintype "passive"))
      (node (ref "U30") (pin "10") (pinfunction "VOUT_3_10") (pintype "passive"))
      (node (ref "U30") (pin "8") (pinfunction "VOUT_1_8") (pintype "passive"))
      (node (ref "U30") (pin "9") (pinfunction "VOUT_2_9") (pintype "passive"))
    )
    (net (code "28") (name "5V0_PS") (class "Default")
      (node (ref "C161") (pin "2") (pinfunction "2_2") (pintype "passive"))
      (node (ref "C162") (pin "2") (pinfunction "2_2") (pintype "passive"))
      (node (ref "C163") (pin "2") (pinfunction "2_2") (pintype "passive"))
      (node (ref "C164") (pin "2") (pinfunction "2_2") (pintype "passive"))
      (node (ref "C165") (pin "2") (pinfunction "2_2") (pintype "passive"))
      (node (ref "C166") (pin "2") (pinfunction "2_2") (pintype "passive"))
      (node (ref "C167") (pin "2") (pinfunction "2_2") (pintype "passive"))
      (node (ref "C168") (pin "2") (pinfunction "2_2") (pintype "passive"))
      (node (ref "C173") (pin "2") (pinfunction "2_2") (pintype "passive"))
      (node (ref "C174") (pin "2") (pinfunction "2_2") (pintype "passive"))
      (node (ref "C175") (pin "2") (pinfunction "2_2") (pintype "passive"))
      (node (ref "C176") (pin "2") (pinfunction "2_2") (pintype "passive"))
      (node (ref "C177") (pin "2") (pinfunction "2_2") (pintype "passive"))
      (node (ref "C178") (pin "2") (pinfunction "2_2") (pintype "passive"))
      (node (ref "C179") (pin "2") (pinfunction "2_2") (pintype "passive"))
      (node (ref "C180") (pin "2") (pinfunction "2_2") (pintype "passive"))
      (node (ref "C181") (pin "2") (pinfunction "2_2") (pintype "passive"))
      (node (ref "L12") (pin "2") (pinfunction "2_2") (pintype "passive"))
      (node (ref "R74") (pin "2") (pinfunction "2_2") (pintype "passive"))
      (node (ref "R75") (pin "1") (pinfunction "1_1") (pintype "passive"))
      (node (ref "TP37") (pin "1") (pinfunction "1_1") (pintype "passive"))
      (node (ref "U3") (pin "25") (pinfunction "SW1FB_25") (pintype "passive"))
    )
    (net (code "29") (name "12V0") (class "Default")
      (node (ref "C149") (pin "2") (pinfunction "2_2") (pintype "passive"))
      (node (ref "C152") (pin "2") (pinfunction "2_2") (pintype "passive"))
      (node (ref "C159") (pin "2") (pinfunction "2_2") (pintype "passive"))
      (node (ref "Q2") (pin "7") (pinfunction "D1_1_7") (pintype "passive"))
      (node (ref "Q2") (pin "8") (pinfunction "D1_2_8") (pintype "passive"))
      (node (ref "Q2") (pin "9") (pinfunction "D1_3_9") (pintype "passive"))
      (node (ref "R63") (pin "2") (pinfunction "2_2") (pintype "passive"))
      (node (ref "TP35") (pin "1") (pinfunction "1_1") (pintype "passive"))
      (node (ref "U3") (pin "18") (pinfunction "SW1IN_1_18") (pintype "passive"))
      (node (ref "U3") (pin "19") (pinfunction "SW1IN_2_19") (pintype "passive"))
      (node (ref "U3") (pin "32") (pinfunction "VIN_32") (pintype "passive"))
    )
    (net (code "30") (name "FLT_12V") (class "Default")
      (node (ref "C151") (pin "1") (pinfunction "1_1") (pintype "passive"))
      (node (ref "FL1") (pin "2") (pinfunction "CB_2") (pintype "passive"))
      (node (ref "R63") (pin "1") (pinfunction "1_1") (pintype "passive"))
      (node (ref "TP34") (pin "1") (pinfunction "1_1") (pintype "passive"))
    )
    (net (code "31") (name "GND") (class "Default")
      (node (ref "C149") (pin "1") (pinfunction "1_1") (pintype "passive"))
      (node (ref "C150") (pin "2") (pinfunction "2_2") (pintype "passive"))
      (node (ref "C151") (pin "2") (pinfunction "2_2") (pintype "passive"))
      (node (ref "C152") (pin "1") (pinfunction "1_1") (pintype "passive"))
      (node (ref "C153") (pin "1") (pinfunction "1_1") (pintype "passive"))
      (node (ref "C154") (pin "1") (pinfunction "1_1") (pintype "passive"))
      (node (ref "C155") (pin "1") (pinfunction "1_1") (pintype "passive"))
      (node (ref "C156") (pin "1") (pinfunction "1_1") (pintype "passive"))
      (node (ref "C157") (pin "1") (pinfunction "1_1") (pintype "passive"))
      (node (ref "C158") (pin "1") (pinfunction "1_1") (pintype "passive"))
      (node (ref "C159") (pin "1") (pinfunction "1_1") (pintype "passive"))
      (node (ref "C161") (pin "1") (pinfunction "1_1") (pintype "passive"))
      (node (ref "C162") (pin "1") (pinfunction "1_1") (pintype "passive"))
      (node (ref "C163") (pin "1") (pinfunction "1_1") (pintype "passive"))
      (node (ref "C164") (pin "1") (pinfunction "1_1") (pintype "passive"))
      (node (ref "C165") (pin "1") (pinfunction "1_1") (pintype "passive"))
      (node (ref "C166") (pin "1") (pinfunction "1_1") (pintype "passive"))
      (node (ref "C167") (pin "1") (pinfunction "1_1") (pintype "passive"))
      (node (ref "C168") (pin "1") (pinfunction "1_1") (pintype "passive"))
      (node (ref "C170") (pin "1") (pinfunction "1_1") (pintype "passive"))
      (node (ref "C171") (pin "1") (pinfunction "1_1") (pintype "passive"))
      (node (ref "C172") (pin "1") (pinfunction "1_1") (pintype "passive"))
      (node (ref "C173") (pin "1") (pinfunction "1_1") (pintype "passive"))
      (node (ref "C174") (pin "1") (pinfunction "1_1") (pintype "passive"))
      (node (ref "C175") (pin "1") (pinfunction "1_1") (pintype "passive"))
      (node (ref "C176") (pin "1") (pinfunction "1_1") (pintype "passive"))
      (node (ref "C177") (pin "1") (pinfunction "1_1") (pintype "passive"))
      (node (ref "C178") (pin "1") (pinfunction "1_1") (pintype "passive"))
      (node (ref "C179") (pin "1") (pinfunction "1_1") (pintype "passive"))
      (node (ref "C180") (pin "1") (pinfunction "1_1") (pintype "passive"))
      (node (ref "C181") (pin "1") (pinfunction "1_1") (pintype "passive"))
      (node (ref "C182") (pin "1") (pinfunction "1_1") (pintype "passive"))
      (node (ref "C183") (pin "1") (pinfunction "1_1") (pintype "passive"))
      (node (ref "C337") (pin "2") (pinfunction "2_2") (pintype "passive"))
      (node (ref "C338") (pin "1") (pinfunction "1_1") (pintype "passive"))
      (node (ref "C339") (pin "1") (pinfunction "1_1") (pintype "passive"))
      (node (ref "C340") (pin "1") (pinfunction "1_1") (pintype "passive"))
      (node (ref "D2") (pin "2") (pinfunction "A_2") (pintype "passive"))
      (node (ref "FL1") (pin "3") (pinfunction "PSG_3") (pintype "passive"))
      (node (ref "FL1") (pin "4") (pinfunction "CG_4") (pintype "passive"))
      (node (ref "FL1") (pin "5") (pinfunction "CG_5") (pintype "passive"))
      (node (ref "FL1") (pin "6") (pinfunction "CG_6") (pintype "passive"))
      (node (ref "J7") (pin "1") (pinfunction "1_1") (pintype "passive"))
      (node (ref "J7") (pin "3") (pinfunction "3_3") (pintype "passive"))
      (node (ref "J7") (pin "S1") (pinfunction "SHIELD_S1") (pintype "passive"))
      (node (ref "J7") (pin "S2") (pinfunction "SHIELD_S2") (pintype "passive"))
      (node (ref "J7") (pin "S3") (pinfunction "SHIELD_S3") (pintype "passive"))
      (node (ref "J8") (pin "2") (pinfunction "2_2") (pintype "passive"))
      (node (ref "Q2") (pin "3") (pinfunction "S2_3") (pintype "passive"))
      (node (ref "R72") (pin "1") (pinfunction "1_1") (pintype "passive"))
      (node (ref "R76") (pin "1") (pinfunction "1_1") (pintype "passive"))
      (node (ref "R77") (pin "1") (pinfunction "1_1") (pintype "passive"))
      (node (ref "R79") (pin "2") (pinfunction "2_2") (pintype "passive"))
      (node (ref "U3") (pin "13") (pinfunction "GPO3_13") (pintype "passive"))
      (node (ref "U3") (pin "14") (pinfunction "GPO2_14") (pintype "passive"))
      (node (ref "U3") (pin "31") (pinfunction "MODE/SYNCIN_31") (pintype "passive"))
      (node (ref "U3") (pin "33") (pinfunction "GND_33") (pintype "passive"))
      (node (ref "U3") (pin "34") (pinfunction "EP_1_34") (pintype "passive"))
      (node (ref "U3") (pin "35") (pinfunction "EP_2_35") (pintype "passive"))
      (node (ref "U3") (pin "36") (pinfunction "EP_3_36") (pintype "passive"))
      (node (ref "U3") (pin "37") (pinfunction "EP_4_37") (pintype "passive"))
      (node (ref "U30") (pin "6") (pinfunction "GND_6") (pintype "passive"))
    )
    (net (code "32") (name "Net-(C183-Pad2)") (class "Default")
      (node (ref "C183") (pin "2") (pinfunction "2_2") (pintype "passive"))
      (node (ref "R78") (pin "1") (pinfunction "1_1") (pintype "passive"))
    )
    (net (code "33") (name "Net-(D19-A)") (class "Default")
      (node (ref "D19") (pin "2") (pinfunction "A_2") (pintype "passive"))
      (node (ref "R235") (pin "2") (pinfunction "2_2") (pintype "passive"))
    )
    (net (code "34") (name "Net-(L11-Pad2)") (class "Default")
      (node (ref "L11") (pin "2") (pinfunction "2_2") (pintype "passive"))
      (node (ref "R64") (pin "I1") (pinfunction "I1_I1") (pintype "passive"))
    )
    (net (code "35") (name "Net-(U3-SW1BOOT)") (class "Default")
      (node (ref "C169") (pin "1") (pinfunction "1_1") (pintype "passive"))
      (node (ref "U3") (pin "17") (pinfunction "SW1BOOT_17") (pintype "passive"))
    )
    (net (code "36") (name "Net-(U3-SW1LX_1)") (class "Default")
      (node (ref "C169") (pin "2") (pinfunction "2_2") (pintype "passive"))
      (node (ref "L12") (pin "1") (pinfunction "1_1") (pintype "passive"))
      (node (ref "U3") (pin "20") (pinfunction "SW1LX_1_20") (pintype "passive"))
      (node (ref "U3") (pin "21") (pinfunction "SW1LX_2_21") (pintype "passive"))
    )
    (net (code "37") (name "Net-(U3-SW2BO_OT)") (class "Default")
      (node (ref "C160") (pin "2") (pinfunction "2_2") (pintype "passive"))
      (node (ref "U3") (pin "12") (pinfunction "SW2BO_OT_12") (pintype "passive"))
    )
    (net (code "38") (name "Net-(U30-CT)") (class "Default")
      (node (ref "C340") (pin "2") (pinfunction "2_2") (pintype "passive"))
      (node (ref "U30") (pin "1") (pinfunction "CT_1") (pintype "passive"))
    )
    (net (code "39") (name "PMIC_VDD_DDRIO") (class "Default")
      (node (ref "R236") (pin "2") (pinfunction "2_2") (pintype "passive"))
    )
    (net (code "40") (name "unconnected-(U30-NC-Pad2)") (class "Default")
      (node (ref "U30") (pin "2") (pinfunction "NC_2") (pintype "passive+no_connect"))
    )
  )
)
